# LittleRC.net
KiCad netlist of a schematic drawn in Altium Designer
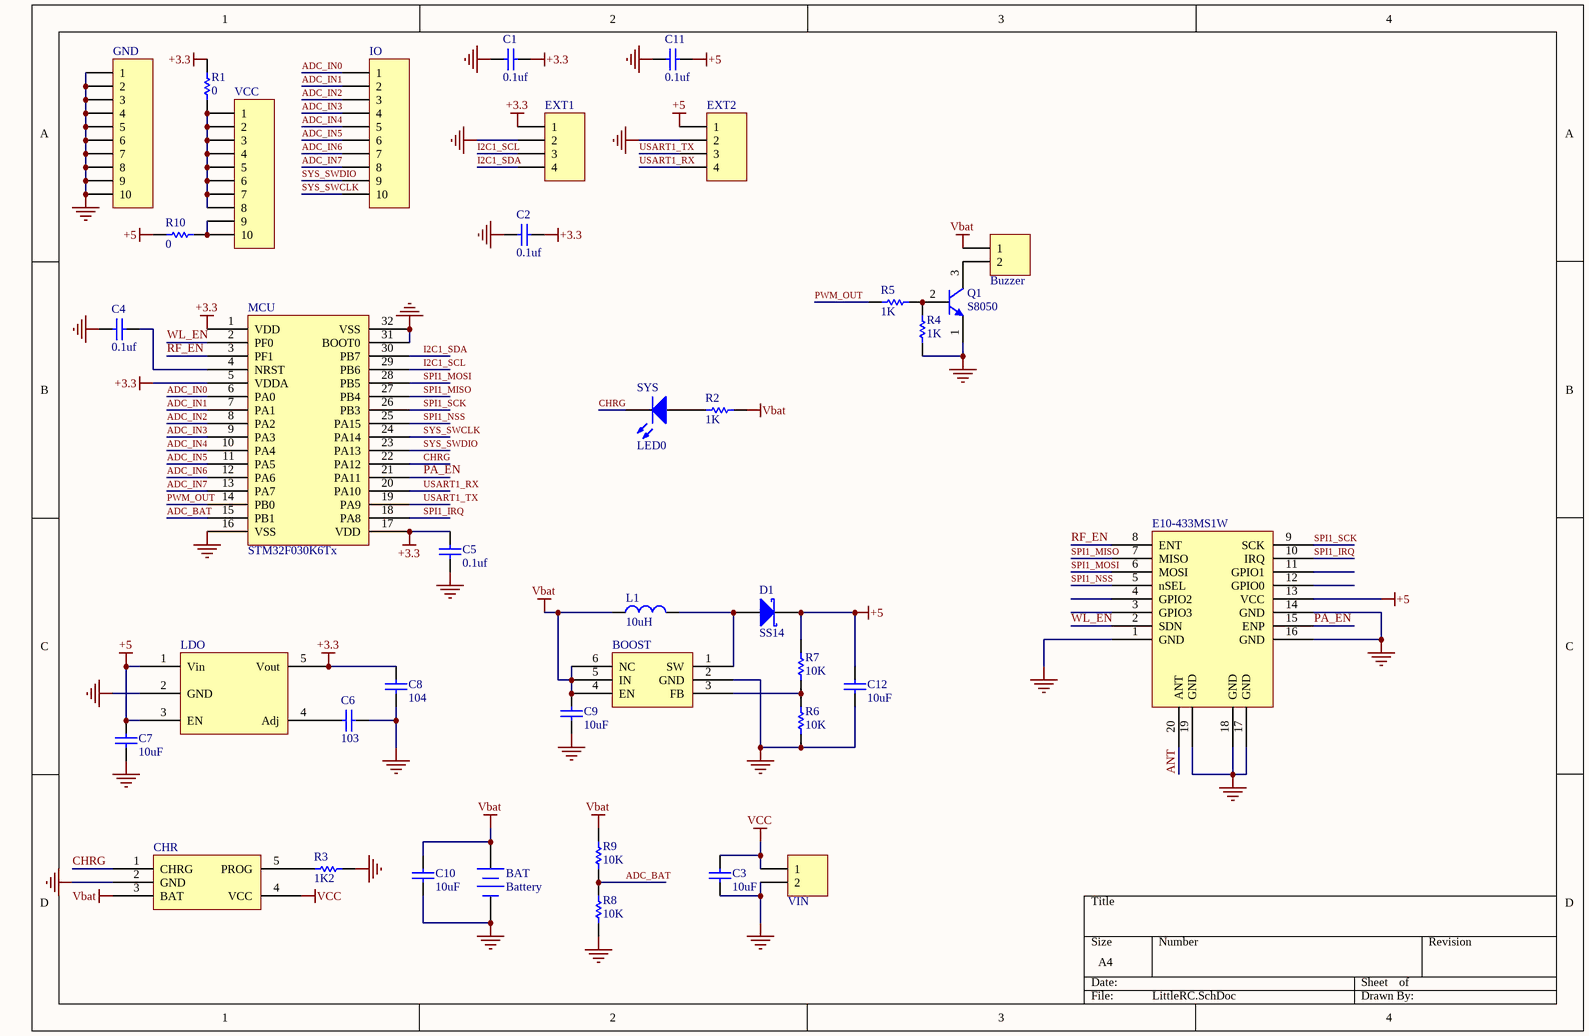
[diagram p0: LittleRC.SchDoc]

(export (version "E")
  (design (tool "Eeschema 10.0.6"))
  (components
    (comp (ref "BAT")
      (value "Battery")
      (footprint "HDR2X1_B1")
      (description "Multicell Battery")
      (fields (field (name "PUBLISHER") "Altium Limited"))
      (libsource (lib "Miscellaneous Devices") (part "Battery"))
    )
    (comp (ref "BOOST") (value "SX1308") (libsource (lib "my") (part "SX1308")))
    (comp (ref "Buzzer")
      (value "Header 2")
      (footprint "HDR2X1_B1")
      (description "接插件")
      (fields (field (name "PUBLISHER") "Altium Limited"))
      (libsource (lib "Genesis") (part "Header 2"))
    )
    (comp (ref "C1")
      (value "0.1uf")
      (footprint "0603-1")
      (description "Capacitor")
      (fields (field (name "Comment") "Cap") (field (name "PUBLISHER") "Altium Limited"))
      (libsource (lib "Miscellaneous Devices") (part "Cap"))
    )
    (comp (ref "C2")
      (value "0.1uf")
      (footprint "CAP-3528")
      (description "Capacitor")
      (fields (field (name "Comment") "Cap") (field (name "PUBLISHER") "Altium Limited"))
      (libsource (lib "Miscellaneous Devices") (part "Cap"))
    )
    (comp (ref "C3")
      (value "10uF")
      (footprint "0603-1")
      (description "Capacitor")
      (fields (field (name "Comment") "Cap") (field (name "PUBLISHER") "Altium Limited"))
      (libsource (lib "Miscellaneous Devices") (part "Cap"))
    )
    (comp (ref "C4")
      (value "0.1uf")
      (footprint "0603-1")
      (description "Capacitor")
      (fields (field (name "Comment") "Cap") (field (name "PUBLISHER") "Altium Limited"))
      (libsource (lib "Miscellaneous Devices") (part "Cap"))
    )
    (comp (ref "C5")
      (value "0.1uf")
      (footprint "0603-1")
      (description "Capacitor")
      (fields (field (name "Comment") "Cap") (field (name "PUBLISHER") "Altium Limited"))
      (libsource (lib "Miscellaneous Devices") (part "Cap"))
    )
    (comp (ref "C6")
      (value "103")
      (footprint "0603-1")
      (description "Capacitor")
      (fields (field (name "Comment") "Cap") (field (name "PUBLISHER") "Altium Limited"))
      (libsource (lib "Miscellaneous Devices") (part "Cap"))
    )
    (comp (ref "C7")
      (value "10uF")
      (footprint "0603-1")
      (description "Capacitor")
      (fields (field (name "Comment") "Cap") (field (name "PUBLISHER") "Altium Limited"))
      (libsource (lib "Miscellaneous Devices") (part "Cap"))
    )
    (comp (ref "C8")
      (value "104")
      (footprint "0603-1")
      (description "Capacitor")
      (fields (field (name "Comment") "Cap") (field (name "PUBLISHER") "Altium Limited"))
      (libsource (lib "Miscellaneous Devices") (part "Cap"))
    )
    (comp (ref "C9")
      (value "10uF")
      (footprint "0603-1")
      (description "Capacitor")
      (fields (field (name "Comment") "Cap") (field (name "PUBLISHER") "Altium Limited"))
      (libsource (lib "Miscellaneous Devices") (part "Cap"))
    )
    (comp (ref "C10")
      (value "10uF")
      (footprint "CAP-3528")
      (description "Capacitor")
      (fields (field (name "Comment") "Cap") (field (name "PUBLISHER") "Altium Limited"))
      (libsource (lib "Miscellaneous Devices") (part "Cap"))
    )
    (comp (ref "C11")
      (value "0.1uf")
      (footprint "0603-1")
      (description "Capacitor")
      (fields (field (name "Comment") "Cap") (field (name "PUBLISHER") "Altium Limited"))
      (libsource (lib "Miscellaneous Devices") (part "Cap"))
    )
    (comp (ref "C12")
      (value "10uF")
      (footprint "RB.1/.2-F")
      (description "Capacitor")
      (fields (field (name "Comment") "Cap") (field (name "PUBLISHER") "Altium Limited"))
      (libsource (lib "Miscellaneous Devices") (part "Cap"))
    )
    (comp (ref "CHR") (value "LTC4054") (footprint "SOT23-5") (libsource (lib "my") (part "LTC4054")))
    (comp (ref "D1")
      (value "D-Schottky")
      (footprint "DIODE-SMA")
      (description "肖特基二极管")
      (fields (field (name "TYPE") "SS14") (field (name "PUBLISHER") "Altium Limited"))
      (libsource (lib "Genesis") (part "D-Schottky"))
    )
    (comp (ref "E10-433MS1W")
      (value "SPI-E10433MS1W")
      (footprint "SPI-E10433MS1W")
      (libsource (lib "my") (part "SPI-E10433MS1W"))
    )
    (comp (ref "EXT1")
      (value "Header 4")
      (footprint "HDR1X4")
      (description "Header, 4-Pin")
      (fields (field (name "PUBLISHER") "Altium Limited"))
      (libsource (lib "Miscellaneous Connectors") (part "Header 4"))
    )
    (comp (ref "EXT2")
      (value "Header 4")
      (footprint "HDR1X4")
      (description "Header, 4-Pin")
      (fields (field (name "PUBLISHER") "Altium Limited"))
      (libsource (lib "Miscellaneous Connectors") (part "Header 4"))
    )
    (comp (ref "GND")
      (value "Header 10")
      (footprint "HDR1X10")
      (description "Header, 10-Pin")
      (fields (field (name "PUBLISHER") "Altium Limited"))
      (libsource (lib "Miscellaneous Connectors") (part "Header 10"))
    )
    (comp (ref "IO")
      (value "Header 10")
      (footprint "HDR1X10")
      (description "Header, 10-Pin")
      (fields (field (name "PUBLISHER") "Altium Limited"))
      (libsource (lib "Miscellaneous Connectors") (part "Header 10"))
    )
    (comp (ref "L1")
      (value "10uH")
      (footprint "0630")
      (description "电感")
      (fields (field (name "Comment") "Inductor") (field (name "PUBLISHER") "Altium Limited"))
      (libsource (lib "Genesis") (part "Inductor"))
    )
    (comp (ref "LDO") (value "SPX3819") (footprint "SOT23-5") (libsource (lib "Schlib1") (part "SPX3819")))
    (comp (ref "MCU")
      (value "STM32F030K6Tx")
      (footprint "LQFP-32")
      (libsource (lib "Schlib1") (part "STM32F030K6Tx"))
    )
    (comp (ref "Q1")
      (value "S8050")
      (footprint "SOT-23")
      (description "NPN三极管")
      (fields (field (name "PUBLISHER") "Altium Limited"))
      (libsource (lib "Genesis") (part "S8050"))
    )
    (comp (ref "R1")
      (value "0")
      (footprint "jumper")
      (description "Resistor")
      (fields (field (name "Comment") "Res1") (field (name "PUBLISHER") "Altium Limited"))
      (libsource (lib "Miscellaneous Devices") (part "Res1"))
    )
    (comp (ref "R2")
      (value "1K")
      (footprint "0603-1")
      (description "Resistor")
      (fields (field (name "Comment") "Res1") (field (name "PUBLISHER") "Altium Limited"))
      (libsource (lib "Miscellaneous Devices") (part "Res1"))
    )
    (comp (ref "R3")
      (value "1K2")
      (footprint "0603-1")
      (description "Resistor")
      (fields (field (name "Comment") "Res1") (field (name "PUBLISHER") "Altium Limited"))
      (libsource (lib "Miscellaneous Devices") (part "Res1"))
    )
    (comp (ref "R4")
      (value "1K")
      (footprint "0603-1")
      (description "Resistor")
      (fields (field (name "Comment") "Res1") (field (name "PUBLISHER") "Altium Limited"))
      (libsource (lib "Miscellaneous Devices") (part "Res1"))
    )
    (comp (ref "R5")
      (value "1K")
      (footprint "0603-1")
      (description "Resistor")
      (fields (field (name "Comment") "Res1") (field (name "PUBLISHER") "Altium Limited"))
      (libsource (lib "Miscellaneous Devices") (part "Res1"))
    )
    (comp (ref "R6")
      (value "10K")
      (footprint "0603-1")
      (description "Resistor")
      (fields (field (name "Comment") "Res1") (field (name "PUBLISHER") "Altium Limited"))
      (libsource (lib "Miscellaneous Devices") (part "Res1"))
    )
    (comp (ref "R7")
      (value "10K")
      (footprint "0603-1")
      (description "Resistor")
      (fields (field (name "Comment") "Res1") (field (name "PUBLISHER") "Altium Limited"))
      (libsource (lib "Miscellaneous Devices") (part "Res1"))
    )
    (comp (ref "R8")
      (value "10K")
      (footprint "0603-1")
      (description "Resistor")
      (fields (field (name "Comment") "Res1") (field (name "PUBLISHER") "Altium Limited"))
      (libsource (lib "Miscellaneous Devices") (part "Res1"))
    )
    (comp (ref "R9")
      (value "10K")
      (footprint "0603-1")
      (description "Resistor")
      (fields (field (name "Comment") "Res1") (field (name "PUBLISHER") "Altium Limited"))
      (libsource (lib "Miscellaneous Devices") (part "Res1"))
    )
    (comp (ref "R10")
      (value "0")
      (footprint "jumper")
      (description "Resistor")
      (fields (field (name "Comment") "Res1") (field (name "PUBLISHER") "Altium Limited"))
      (libsource (lib "Miscellaneous Devices") (part "Res1"))
    )
    (comp (ref "SYS")
      (value "LED0")
      (footprint "0603-1")
      (description "Typical INFRARED GaAs LED")
      (fields (field (name "PUBLISHER") "Altium Limited"))
      (libsource (lib "Miscellaneous Devices") (part "LED0"))
    )
    (comp (ref "VCC")
      (value "Header 10")
      (footprint "HDR1X10")
      (description "Header, 10-Pin")
      (fields (field (name "PUBLISHER") "Altium Limited"))
      (libsource (lib "Miscellaneous Connectors") (part "Header 10"))
    )
    (comp (ref "VIN")
      (value "Header 2")
      (footprint "HDR2X1_B1")
      (description "接插件")
      (fields (field (name "PUBLISHER") "Altium Limited"))
      (libsource (lib "Genesis") (part "Header 2"))
    )
  )
  (nets
    (net (code "1") (name "+3.3") (class "Default")
      (node (ref "C1") (pin "1") (pinfunction "1_1") (pintype "passive"))
      (node (ref "C2") (pin "1") (pinfunction "1_1") (pintype "passive"))
      (node (ref "C5") (pin "2") (pinfunction "2_2") (pintype "passive"))
      (node (ref "C8") (pin "2") (pinfunction "2_2") (pintype "passive"))
      (node (ref "EXT1") (pin "1") (pinfunction "1_1") (pintype "passive"))
      (node (ref "LDO") (pin "5") (pinfunction "Vout_5") (pintype "passive"))
      (node (ref "MCU") (pin "1") (pinfunction "VDD_1") (pintype "passive"))
      (node (ref "MCU") (pin "17") (pinfunction "VDD_17") (pintype "passive"))
      (node (ref "MCU") (pin "5") (pinfunction "VDDA_5") (pintype "passive"))
      (node (ref "R1") (pin "2") (pinfunction "2_2") (pintype "passive"))
    )
    (net (code "2") (name "+5") (class "Default")
      (node (ref "C11") (pin "1") (pinfunction "1_1") (pintype "passive"))
      (node (ref "C12") (pin "2") (pinfunction "2_2") (pintype "passive"))
      (node (ref "C7") (pin "2") (pinfunction "2_2") (pintype "passive"))
      (node (ref "D1") (pin "2") (pinfunction "K_2") (pintype "passive"))
      (node (ref "E10-433MS1W") (pin "13") (pinfunction "VCC_13") (pintype "passive"))
      (node (ref "EXT2") (pin "1") (pinfunction "1_1") (pintype "passive"))
      (node (ref "LDO") (pin "1") (pinfunction "Vin_1") (pintype "passive"))
      (node (ref "LDO") (pin "3") (pinfunction "EN_3") (pintype "passive"))
      (node (ref "R10") (pin "2") (pinfunction "2_2") (pintype "passive"))
      (node (ref "R7") (pin "2") (pinfunction "2_2") (pintype "passive"))
    )
    (net (code "3") (name "/ADC_BAT") (class "Default")
      (node (ref "MCU") (pin "15") (pinfunction "PB1_15") (pintype "passive"))
      (node (ref "R8") (pin "1") (pinfunction "1_1") (pintype "passive"))
      (node (ref "R9") (pin "2") (pinfunction "2_2") (pintype "passive"))
    )
    (net (code "4") (name "/ADC_IN0") (class "Default")
      (node (ref "IO") (pin "1") (pinfunction "1_1") (pintype "passive"))
      (node (ref "MCU") (pin "6") (pinfunction "PA0_6") (pintype "passive"))
    )
    (net (code "5") (name "/ADC_IN1") (class "Default")
      (node (ref "IO") (pin "2") (pinfunction "2_2") (pintype "passive"))
      (node (ref "MCU") (pin "7") (pinfunction "PA1_7") (pintype "passive"))
    )
    (net (code "6") (name "/ADC_IN2") (class "Default")
      (node (ref "IO") (pin "3") (pinfunction "3_3") (pintype "passive"))
      (node (ref "MCU") (pin "8") (pinfunction "PA2_8") (pintype "passive"))
    )
    (net (code "7") (name "/ADC_IN3") (class "Default")
      (node (ref "IO") (pin "4") (pinfunction "4_4") (pintype "passive"))
      (node (ref "MCU") (pin "9") (pinfunction "PA3_9") (pintype "passive"))
    )
    (net (code "8") (name "/ADC_IN4") (class "Default")
      (node (ref "IO") (pin "5") (pinfunction "5_5") (pintype "passive"))
      (node (ref "MCU") (pin "10") (pinfunction "PA4_10") (pintype "passive"))
    )
    (net (code "9") (name "/ADC_IN5") (class "Default")
      (node (ref "IO") (pin "6") (pinfunction "6_6") (pintype "passive"))
      (node (ref "MCU") (pin "11") (pinfunction "PA5_11") (pintype "passive"))
    )
    (net (code "10") (name "/ADC_IN6") (class "Default")
      (node (ref "IO") (pin "7") (pinfunction "7_7") (pintype "passive"))
      (node (ref "MCU") (pin "12") (pinfunction "PA6_12") (pintype "passive"))
    )
    (net (code "11") (name "/ADC_IN7") (class "Default")
      (node (ref "IO") (pin "8") (pinfunction "8_8") (pintype "passive"))
      (node (ref "MCU") (pin "13") (pinfunction "PA7_13") (pintype "passive"))
    )
    (net (code "12") (name "/ANT") (class "Default")
      (node (ref "E10-433MS1W") (pin "20") (pinfunction "ANT_20") (pintype "passive"))
    )
    (net (code "13") (name "/CHRG") (class "Default")
      (node (ref "CHR") (pin "1") (pinfunction "CHRG_1") (pintype "passive"))
      (node (ref "MCU") (pin "22") (pinfunction "PA12_22") (pintype "passive"))
      (node (ref "SYS") (pin "2") (pinfunction "K_2") (pintype "passive"))
    )
    (net (code "14") (name "/I2C1_SCL") (class "Default")
      (node (ref "EXT1") (pin "3") (pinfunction "3_3") (pintype "passive"))
      (node (ref "MCU") (pin "29") (pinfunction "PB6_29") (pintype "passive"))
    )
    (net (code "15") (name "/I2C1_SDA") (class "Default")
      (node (ref "EXT1") (pin "4") (pinfunction "4_4") (pintype "passive"))
      (node (ref "MCU") (pin "30") (pinfunction "PB7_30") (pintype "passive"))
    )
    (net (code "16") (name "/PA_EN") (class "Default")
      (node (ref "E10-433MS1W") (pin "15") (pinfunction "ENP_15") (pintype "passive"))
      (node (ref "MCU") (pin "21") (pinfunction "PA11_21") (pintype "passive"))
    )
    (net (code "17") (name "/PWM_OUT") (class "Default")
      (node (ref "MCU") (pin "14") (pinfunction "PB0_14") (pintype "passive"))
      (node (ref "R5") (pin "2") (pinfunction "2_2") (pintype "passive"))
    )
    (net (code "18") (name "/RF_EN") (class "Default")
      (node (ref "E10-433MS1W") (pin "8") (pinfunction "ENT_8") (pintype "passive"))
      (node (ref "MCU") (pin "3") (pinfunction "PF1_3") (pintype "passive"))
    )
    (net (code "19") (name "/SPI1_IRQ") (class "Default")
      (node (ref "E10-433MS1W") (pin "10") (pinfunction "IRQ_10") (pintype "passive"))
      (node (ref "MCU") (pin "18") (pinfunction "PA8_18") (pintype "passive"))
    )
    (net (code "20") (name "/SPI1_MISO") (class "Default")
      (node (ref "E10-433MS1W") (pin "7") (pinfunction "MISO_7") (pintype "passive"))
      (node (ref "MCU") (pin "27") (pinfunction "PB4_27") (pintype "passive"))
    )
    (net (code "21") (name "/SPI1_MOSI") (class "Default")
      (node (ref "E10-433MS1W") (pin "6") (pinfunction "MOSI_6") (pintype "passive"))
      (node (ref "MCU") (pin "28") (pinfunction "PB5_28") (pintype "passive"))
    )
    (net (code "22") (name "/SPI1_NSS") (class "Default")
      (node (ref "E10-433MS1W") (pin "5") (pinfunction "nSEL_5") (pintype "passive"))
      (node (ref "MCU") (pin "25") (pinfunction "PA15_25") (pintype "passive"))
    )
    (net (code "23") (name "/SPI1_SCK") (class "Default")
      (node (ref "E10-433MS1W") (pin "9") (pinfunction "SCK_9") (pintype "passive"))
      (node (ref "MCU") (pin "26") (pinfunction "PB3_26") (pintype "passive"))
    )
    (net (code "24") (name "/SYS_SWCLK") (class "Default")
      (node (ref "IO") (pin "10") (pinfunction "10_10") (pintype "passive"))
      (node (ref "MCU") (pin "24") (pinfunction "PA14_24") (pintype "passive"))
    )
    (net (code "25") (name "/SYS_SWDIO") (class "Default")
      (node (ref "IO") (pin "9") (pinfunction "9_9") (pintype "passive"))
      (node (ref "MCU") (pin "23") (pinfunction "PA13_23") (pintype "passive"))
    )
    (net (code "26") (name "/USART1_RX") (class "Default")
      (node (ref "EXT2") (pin "4") (pinfunction "4_4") (pintype "passive"))
      (node (ref "MCU") (pin "20") (pinfunction "PA10_20") (pintype "passive"))
    )
    (net (code "27") (name "/USART1_TX") (class "Default")
      (node (ref "EXT2") (pin "3") (pinfunction "3_3") (pintype "passive"))
      (node (ref "MCU") (pin "19") (pinfunction "PA9_19") (pintype "passive"))
    )
    (net (code "28") (name "/WL_EN") (class "Default")
      (node (ref "E10-433MS1W") (pin "2") (pinfunction "SDN_2") (pintype "passive"))
      (node (ref "MCU") (pin "2") (pinfunction "PF0_2") (pintype "passive"))
    )
    (net (code "29") (name "GND") (class "Default")
      (node (ref "BAT") (pin "2") (pinfunction "-_2") (pintype "passive"))
      (node (ref "BOOST") (pin "2") (pinfunction "GND_2") (pintype "passive"))
      (node (ref "C1") (pin "2") (pinfunction "2_2") (pintype "passive"))
      (node (ref "C10") (pin "1") (pinfunction "1_1") (pintype "passive"))
      (node (ref "C11") (pin "2") (pinfunction "2_2") (pintype "passive"))
      (node (ref "C12") (pin "1") (pinfunction "1_1") (pintype "passive"))
      (node (ref "C2") (pin "2") (pinfunction "2_2") (pintype "passive"))
      (node (ref "C3") (pin "1") (pinfunction "1_1") (pintype "passive"))
      (node (ref "C4") (pin "2") (pinfunction "2_2") (pintype "passive"))
      (node (ref "C5") (pin "1") (pinfunction "1_1") (pintype "passive"))
      (node (ref "C6") (pin "1") (pinfunction "1_1") (pintype "passive"))
      (node (ref "C7") (pin "1") (pinfunction "1_1") (pintype "passive"))
      (node (ref "C8") (pin "1") (pinfunction "1_1") (pintype "passive"))
      (node (ref "C9") (pin "1") (pinfunction "1_1") (pintype "passive"))
      (node (ref "CHR") (pin "2") (pinfunction "GND_2") (pintype "passive"))
      (node (ref "E10-433MS1W") (pin "1") (pinfunction "GND_1") (pintype "passive"))
      (node (ref "E10-433MS1W") (pin "14") (pinfunction "GND_14") (pintype "passive"))
      (node (ref "E10-433MS1W") (pin "16") (pinfunction "GND_16") (pintype "passive"))
      (node (ref "E10-433MS1W") (pin "17") (pinfunction "GND_17") (pintype "passive"))
      (node (ref "E10-433MS1W") (pin "18") (pinfunction "GND_18") (pintype "passive"))
      (node (ref "E10-433MS1W") (pin "19") (pinfunction "GND_19") (pintype "passive"))
      (node (ref "EXT1") (pin "2") (pinfunction "2_2") (pintype "passive"))
      (node (ref "EXT2") (pin "2") (pinfunction "2_2") (pintype "passive"))
      (node (ref "GND") (pin "1") (pinfunction "1_1") (pintype "passive"))
      (node (ref "GND") (pin "10") (pinfunction "10_10") (pintype "passive"))
      (node (ref "GND") (pin "2") (pinfunction "2_2") (pintype "passive"))
      (node (ref "GND") (pin "3") (pinfunction "3_3") (pintype "passive"))
      (node (ref "GND") (pin "4") (pinfunction "4_4") (pintype "passive"))
      (node (ref "GND") (pin "5") (pinfunction "5_5") (pintype "passive"))
      (node (ref "GND") (pin "6") (pinfunction "6_6") (pintype "passive"))
      (node (ref "GND") (pin "7") (pinfunction "7_7") (pintype "passive"))
      (node (ref "GND") (pin "8") (pinfunction "8_8") (pintype "passive"))
      (node (ref "GND") (pin "9") (pinfunction "9_9") (pintype "passive"))
      (node (ref "LDO") (pin "2") (pinfunction "GND_2") (pintype "passive"))
      (node (ref "MCU") (pin "16") (pinfunction "VSS_16") (pintype "passive"))
      (node (ref "MCU") (pin "31") (pinfunction "BOOT0_31") (pintype "passive"))
      (node (ref "MCU") (pin "32") (pinfunction "VSS_32") (pintype "passive"))
      (node (ref "Q1") (pin "1") (pinfunction "E_1") (pintype "passive"))
      (node (ref "R3") (pin "2") (pinfunction "2_2") (pintype "passive"))
      (node (ref "R4") (pin "2") (pinfunction "2_2") (pintype "passive"))
      (node (ref "R6") (pin "1") (pinfunction "1_1") (pintype "passive"))
      (node (ref "R8") (pin "2") (pinfunction "2_2") (pintype "passive"))
      (node (ref "VIN") (pin "2") (pinfunction "2_2") (pintype "passive"))
    )
    (net (code "30") (name "Net-(BOOST-FB)") (class "Default")
      (node (ref "BOOST") (pin "3") (pinfunction "FB_3") (pintype "passive"))
      (node (ref "R6") (pin "2") (pinfunction "2_2") (pintype "passive"))
      (node (ref "R7") (pin "1") (pinfunction "1_1") (pintype "passive"))
    )
    (net (code "31") (name "Net-(BOOST-SW)") (class "Default")
      (node (ref "BOOST") (pin "1") (pinfunction "SW_1") (pintype "passive"))
      (node (ref "D1") (pin "1") (pinfunction "A_1") (pintype "passive"))
      (node (ref "L1") (pin "2") (pinfunction "2_2") (pintype "passive"))
    )
    (net (code "32") (name "Net-(CHR-PROG)") (class "Default")
      (node (ref "CHR") (pin "5") (pinfunction "PROG_5") (pintype "passive"))
      (node (ref "R3") (pin "1") (pinfunction "1_1") (pintype "passive"))
    )
    (net (code "33") (name "Net-(LDO-Adj)") (class "Default")
      (node (ref "C6") (pin "2") (pinfunction "2_2") (pintype "passive"))
      (node (ref "LDO") (pin "4") (pinfunction "Adj_4") (pintype "passive"))
    )
    (net (code "34") (name "Net-(MCU-NRST)") (class "Default")
      (node (ref "C4") (pin "1") (pinfunction "1_1") (pintype "passive"))
      (node (ref "MCU") (pin "4") (pinfunction "NRST_4") (pintype "passive"))
    )
    (net (code "35") (name "Net-(Q1-B)") (class "Default")
      (node (ref "Q1") (pin "2") (pinfunction "B_2") (pintype "passive"))
      (node (ref "R4") (pin "1") (pinfunction "1_1") (pintype "passive"))
      (node (ref "R5") (pin "1") (pinfunction "1_1") (pintype "passive"))
    )
    (net (code "36") (name "Net-(Q1-C)") (class "Default")
      (node (ref "Buzzer") (pin "2") (pinfunction "2_2") (pintype "passive"))
      (node (ref "Q1") (pin "3") (pinfunction "C_3") (pintype "passive"))
    )
    (net (code "37") (name "Net-(R1-Pad1)") (class "Default")
      (node (ref "R1") (pin "1") (pinfunction "1_1") (pintype "passive"))
      (node (ref "VCC") (pin "1") (pinfunction "1_1") (pintype "passive"))
      (node (ref "VCC") (pin "2") (pinfunction "2_2") (pintype "passive"))
      (node (ref "VCC") (pin "3") (pinfunction "3_3") (pintype "passive"))
      (node (ref "VCC") (pin "4") (pinfunction "4_4") (pintype "passive"))
      (node (ref "VCC") (pin "5") (pinfunction "5_5") (pintype "passive"))
      (node (ref "VCC") (pin "6") (pinfunction "6_6") (pintype "passive"))
      (node (ref "VCC") (pin "7") (pinfunction "7_7") (pintype "passive"))
      (node (ref "VCC") (pin "8") (pinfunction "8_8") (pintype "passive"))
    )
    (net (code "38") (name "Net-(R10-Pad1)") (class "Default")
      (node (ref "R10") (pin "1") (pinfunction "1_1") (pintype "passive"))
      (node (ref "VCC") (pin "10") (pinfunction "10_10") (pintype "passive"))
      (node (ref "VCC") (pin "9") (pinfunction "9_9") (pintype "passive"))
    )
    (net (code "39") (name "Net-(SYS-A)") (class "Default")
      (node (ref "R2") (pin "2") (pinfunction "2_2") (pintype "passive"))
      (node (ref "SYS") (pin "1") (pinfunction "A_1") (pintype "passive"))
    )
    (net (code "40") (name "VCC") (class "Default")
      (node (ref "C3") (pin "2") (pinfunction "2_2") (pintype "passive"))
      (node (ref "CHR") (pin "4") (pinfunction "VCC_4") (pintype "passive"))
      (node (ref "VIN") (pin "1") (pinfunction "1_1") (pintype "passive"))
    )
    (net (code "41") (name "Vbat") (class "Default")
      (node (ref "BAT") (pin "1") (pinfunction "+_1") (pintype "passive"))
      (node (ref "BOOST") (pin "4") (pinfunction "EN_4") (pintype "passive"))
      (node (ref "BOOST") (pin "5") (pinfunction "IN_5") (pintype "passive"))
      (node (ref "BOOST") (pin "6") (pinfunction "NC_6") (pintype "passive"))
      (node (ref "Buzzer") (pin "1") (pinfunction "1_1") (pintype "passive"))
      (node (ref "C10") (pin "2") (pinfunction "2_2") (pintype "passive"))
      (node (ref "C9") (pin "2") (pinfunction "2_2") (pintype "passive"))
      (node (ref "CHR") (pin "3") (pinfunction "BAT_3") (pintype "passive"))
      (node (ref "L1") (pin "1") (pinfunction "1_1") (pintype "passive"))
      (node (ref "R2") (pin "1") (pinfunction "1_1") (pintype "passive"))
      (node (ref "R9") (pin "1") (pinfunction "1_1") (pintype "passive"))
    )
    (net (code "42") (name "unconnected-(E10-433MS1W-GPIO0-Pad12)") (class "Default")
      (node (ref "E10-433MS1W") (pin "12") (pinfunction "GPIO0_12") (pintype "passive"))
    )
    (net (code "43") (name "unconnected-(E10-433MS1W-GPIO1-Pad11)") (class "Default")
      (node (ref "E10-433MS1W") (pin "11") (pinfunction "GPIO1_11") (pintype "passive"))
    )
    (net (code "44") (name "unconnected-(E10-433MS1W-GPIO2-Pad4)") (class "Default")
      (node (ref "E10-433MS1W") (pin "4") (pinfunction "GPIO2_4") (pintype "passive"))
    )
    (net (code "45") (name "unconnected-(E10-433MS1W-GPIO3-Pad3)") (class "Default")
      (node (ref "E10-433MS1W") (pin "3") (pinfunction "GPIO3_3") (pintype "passive"))
    )
  )
)
